# custom_pcb_schematic.net
KiCad netlist of a schematic drawn in Altium Designer
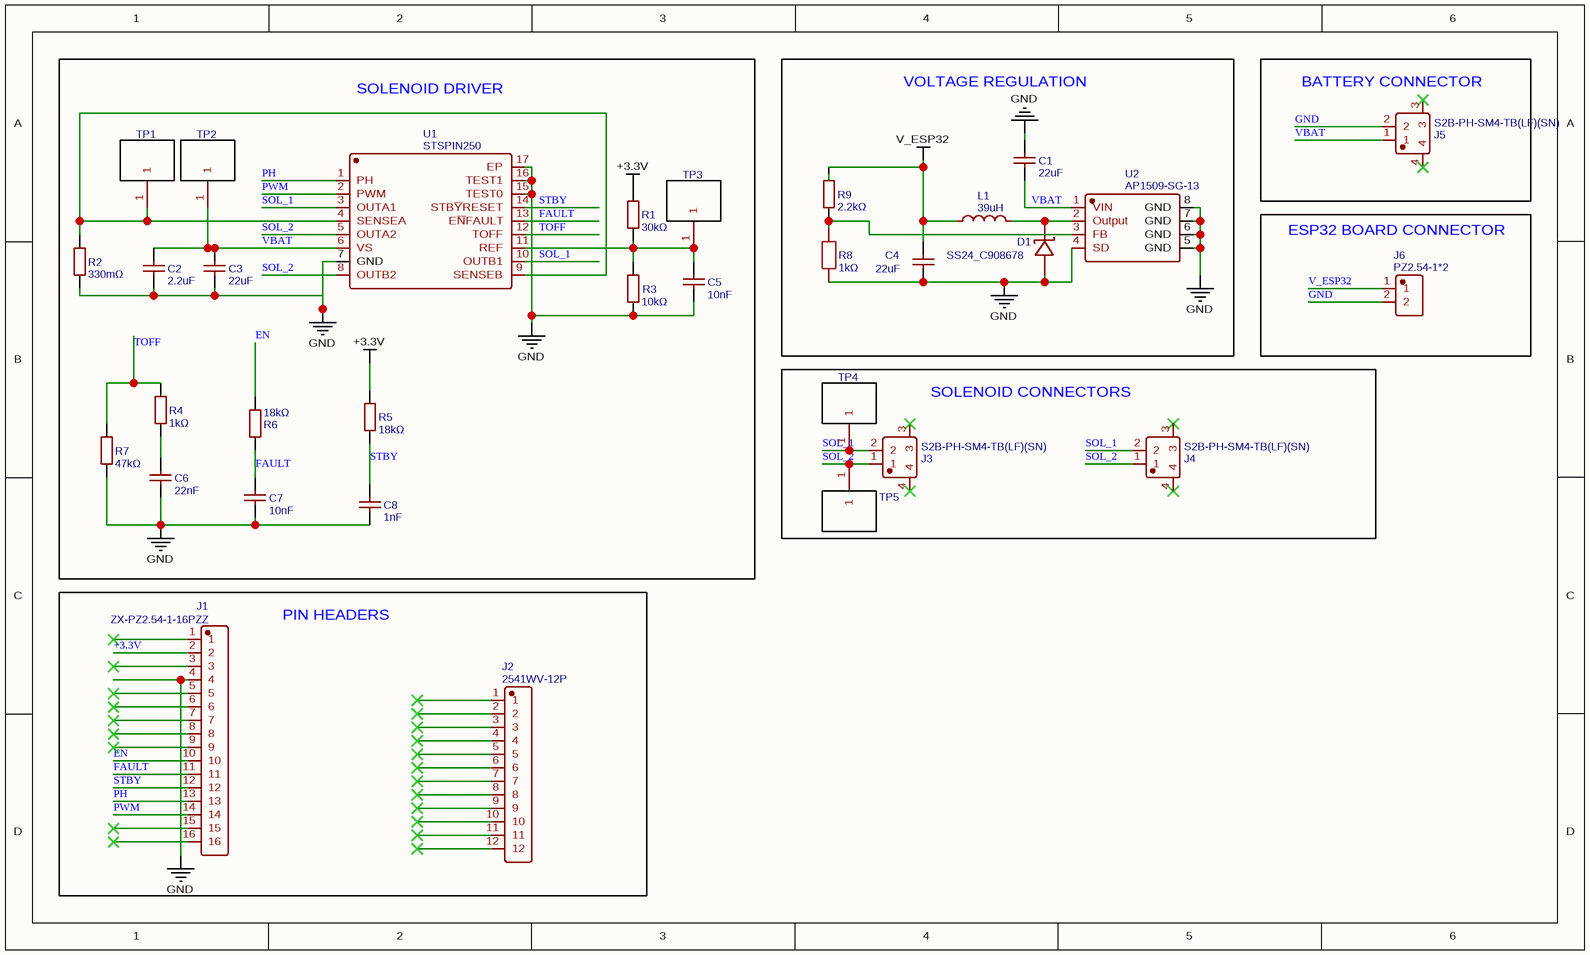
[diagram p0: custom_pcb_schematic.schdoc]

(export (version "E")
  (design (tool "Eeschema 10.0.6"))
  (components
    (comp (ref "C1")
      (value "22uF")
      (fields
        (field (name "MANUFACTURER") "SAMSUNG(三星)")
        (field (name "MANUFACTURER PART") "CL21A226MOQNNNE")
      )
      (libsource (lib "altium-import") (part "root_1_22uF_"))
    )
    (comp (ref "C2")
      (value "2.2uF")
      (fields
        (field (name "MANUFACTURER PART") "CL10A225KO8NNNC")
        (field (name "MANUFACTURER") "SAMSUNG(三星)")
      )
      (libsource (lib "altium-import") (part "root_1_2.2uF_"))
    )
    (comp (ref "C3")
      (value "22uF")
      (fields
        (field (name "MANUFACTURER") "SAMSUNG(三星)")
        (field (name "MANUFACTURER PART") "CL21A226MOQNNNE")
      )
      (libsource (lib "altium-import") (part "root_1_22uF_"))
    )
    (comp (ref "C4")
      (value "22uF")
      (fields
        (field (name "MANUFACTURER") "SAMSUNG(三星)")
        (field (name "MANUFACTURER PART") "CL21A226MOQNNNE")
      )
      (libsource (lib "altium-import") (part "root_1_22uF_"))
    )
    (comp (ref "C5")
      (value "10nF")
      (fields
        (field (name "MANUFACTURER PART") "CL10B103KB8NNNC")
        (field (name "MANUFACTURER") "SAMSUNG(三星)")
      )
      (libsource (lib "altium-import") (part "root_1_10nF_"))
    )
    (comp (ref "C6")
      (value "22nF")
      (fields
        (field (name "MANUFACTURER PART") "CL10B223KB8NNNC")
        (field (name "MANUFACTURER") "SAMSUNG(三星)")
      )
      (libsource (lib "altium-import") (part "root_1_22nF_"))
    )
    (comp (ref "C7")
      (value "10nF")
      (fields
        (field (name "MANUFACTURER PART") "CL10B103KB8NNNC")
        (field (name "MANUFACTURER") "SAMSUNG(三星)")
      )
      (libsource (lib "altium-import") (part "root_1_10nF_"))
    )
    (comp (ref "C8")
      (value "1nF")
      (fields
        (field (name "MANUFACTURER") "YAGEO(国巨)")
        (field (name "MANUFACTURER PART") "CC0402KRX7R9BB102")
        (field (name "CONTRIBUTOR") "LCSC")
      )
      (libsource (lib "altium-import") (part "root_1_1nF_"))
    )
    (comp (ref "D1")
      (value "SS24_C908678")
      (fields
        (field (name "MANUFACTURER") "GOODWORK(固得沃克)")
        (field (name "MANUFACTURER PART") "SS24")
        (field (name "CONTRIBUTOR") "lcsc")
      )
      (libsource (lib "altium-import") (part "root_3_SS24_C908678_"))
    )
    (comp (ref "J1")
      (value "ZX-PZ2.54-1-16PZZ")
      (fields (field (name "MANUFACTURER") "Megastar(兆星)") (field (name "CONTRIBUTOR") "lcsc"))
      (libsource (lib "altium-import") (part "root_0_ZX-PZ2.54-1-16PZZ_"))
    )
    (comp (ref "J2")
      (value "2541WV-12P")
      (fields (field (name "MANUFACTURER") "HanElectricity(瀚源)") (field (name "CONTRIBUTOR") "lcsc"))
      (libsource (lib "altium-import") (part "root_0_2541WV-12P_"))
    )
    (comp (ref "J3")
      (value "S2B-PH-SM4-TB(LF)(SN)")
      (fields (field (name "MANUFACTURER") "JST") (field (name "CONTRIBUTOR") "LCSC"))
      (libsource (lib "altium-import") (part "root_0_S2B-PH-SM4-TB(LF)(SN)_"))
    )
    (comp (ref "J4")
      (value "S2B-PH-SM4-TB(LF)(SN)")
      (fields (field (name "MANUFACTURER") "JST") (field (name "CONTRIBUTOR") "LCSC"))
      (libsource (lib "altium-import") (part "root_0_S2B-PH-SM4-TB(LF)(SN)_"))
    )
    (comp (ref "J5")
      (value "S2B-PH-SM4-TB(LF)(SN)")
      (fields (field (name "MANUFACTURER") "JST") (field (name "CONTRIBUTOR") "LCSC"))
      (libsource (lib "altium-import") (part "root_0_S2B-PH-SM4-TB(LF)(SN)_"))
    )
    (comp (ref "J6")
      (value "PZ2.54-1*2")
      (fields (field (name "MANUFACTURER") "ZHOURI(洲日)") (field (name "CONTRIBUTOR") "lcsc"))
      (libsource (lib "altium-import") (part "root_0_PZ2.54-1*2_"))
    )
    (comp (ref "L1")
      (value "39uH")
      (fields
        (field (name "MANUFACTURER") "YJYCOIN(益嘉源)")
        (field (name "MANUFACTURER PART") "YDRH104R-390M")
        (field (name "CONTRIBUTOR") "LCSC")
      )
      (libsource (lib "altium-import") (part "root_0_39uH_"))
    )
    (comp (ref "R1")
      (value "30kΩ")
      (fields (field (name "MANUFACTURER") "YAGEO(国巨)") (field (name "MANUFACTURER PART") "RC0402FR-0730KL"))
      (libsource (lib "altium-import") (part "root_1_30kΩ_"))
    )
    (comp (ref "R2")
      (value "330mΩ")
      (fields
        (field (name "MANUFACTURER") "UNI-ROYAL(厚声)")
        (field (name "MANUFACTURER PART") "25121WF330LT4E")
      )
      (libsource (lib "altium-import") (part "root_1_330mΩ_"))
    )
    (comp (ref "R3")
      (value "10kΩ")
      (fields
        (field (name "MANUFACTURER") "UNI-ROYAL(厚声)")
        (field (name "MANUFACTURER PART") "0603WAF1002T5E")
      )
      (libsource (lib "altium-import") (part "root_1_10kΩ_"))
    )
    (comp (ref "R4")
      (value "1kΩ")
      (fields (field (name "MANUFACTURER PART") "RC0603FR-071KL") (field (name "MANUFACTURER") "YAGEO(国巨)"))
      (libsource (lib "") (part "root_1_1kΩ__1"))
    )
    (comp (ref "R5")
      (value "18kΩ")
      (fields (field (name "MANUFACTURER") "YAGEO(国巨)") (field (name "MANUFACTURER PART") "RC0402FR-0718KL"))
      (libsource (lib "") (part "root_1_18kΩ__1"))
    )
    (comp (ref "R6")
      (value "18kΩ")
      (fields (field (name "MANUFACTURER") "YAGEO(国巨)") (field (name "MANUFACTURER PART") "RC0402FR-0718KL"))
      (libsource (lib "altium-import") (part "root_1_18kΩ_"))
    )
    (comp (ref "R7")
      (value "47kΩ")
      (fields (field (name "MANUFACTURER") "YAGEO(国巨)") (field (name "MANUFACTURER PART") "RC0402FR-0747KL"))
      (libsource (lib "altium-import") (part "root_1_47kΩ_"))
    )
    (comp (ref "R8")
      (value "1kΩ")
      (fields
        (field (name "MANUFACTURER") "VO(翔胜)")
        (field (name "MANUFACTURER PART") "SCR0603F1K")
        (field (name "CONTRIBUTOR") "lcsc")
      )
      (libsource (lib "altium-import") (part "root_1_1kΩ_"))
    )
    (comp (ref "R9")
      (value "2.2kΩ")
      (fields (field (name "MANUFACTURER") "YAGEO(国巨)") (field (name "MANUFACTURER PART") "RC0402FR-072K2L"))
      (libsource (lib "altium-import") (part "root_1_2.2kΩ_"))
    )
    (comp (ref "TP1")
      (value "PG2.0-4.5-0.8T")
      (fields (field (name "CONTRIBUTOR") "LCSC"))
      (libsource (lib "altium-import") (part "root_3_PG2.0-4.5-0.8T_"))
    )
    (comp (ref "TP2")
      (value "PG2.0-4.5-0.8T")
      (fields (field (name "CONTRIBUTOR") "LCSC"))
      (libsource (lib "altium-import") (part "root_3_PG2.0-4.5-0.8T_"))
    )
    (comp (ref "TP3")
      (value "PG2.0-4.5-0.8T")
      (fields (field (name "CONTRIBUTOR") "LCSC"))
      (libsource (lib "altium-import") (part "root_3_PG2.0-4.5-0.8T_"))
    )
    (comp (ref "TP4")
      (value "PG2.0-4.5-0.8T")
      (fields (field (name "CONTRIBUTOR") "LCSC"))
      (libsource (lib "altium-import") (part "root_3_PG2.0-4.5-0.8T_"))
    )
    (comp (ref "TP5")
      (value "PG2.0-4.5-0.8T")
      (fields (field (name "CONTRIBUTOR") "LCSC"))
      (libsource (lib "altium-import") (part "root_1_PG2.0-4.5-0.8T_"))
    )
    (comp (ref "U1")
      (value "STSPIN250")
      (fields (field (name "MANUFACTURER") "ST(意法半导体)") (field (name "CONTRIBUTOR") "LCSC"))
      (libsource (lib "altium-import") (part "root_0_STSPIN250_"))
    )
    (comp (ref "U2")
      (value "AP1509-SG-13")
      (fields (field (name "MANUFACTURER") "DIODES(美台)") (field (name "CONTRIBUTOR") "lcsc"))
      (libsource (lib "altium-import") (part "root_0_AP1509-SG-13_"))
    )
  )
  (nets
    (net (code "1") (name "+3.3V") (class "Default")
      (node (ref "J1") (pin "2") (pinfunction "2_2") (pintype "passive"))
      (node (ref "R1") (pin "2") (pinfunction "2_2") (pintype "passive"))
      (node (ref "R5") (pin "2") (pinfunction "2_2") (pintype "passive"))
    )
    (net (code "2") (name "/EN") (class "Default")
      (node (ref "J1") (pin "10") (pinfunction "10_10") (pintype "passive"))
      (node (ref "R6") (pin "1") (pinfunction "1_1") (pintype "passive"))
    )
    (net (code "3") (name "/FAULT") (class "Default")
      (node (ref "C7") (pin "2") (pinfunction "2_2") (pintype "passive"))
      (node (ref "J1") (pin "11") (pinfunction "11_11") (pintype "passive"))
      (node (ref "R6") (pin "2") (pinfunction "2_2") (pintype "passive"))
      (node (ref "U1") (pin "13") (pinfunction "E~{N}FAULT_13") (pintype "passive"))
    )
    (net (code "4") (name "/PH") (class "Default")
      (node (ref "J1") (pin "13") (pinfunction "13_13") (pintype "passive"))
      (node (ref "U1") (pin "1") (pinfunction "PH_1") (pintype "passive"))
    )
    (net (code "5") (name "/PWM") (class "Default")
      (node (ref "J1") (pin "14") (pinfunction "14_14") (pintype "passive"))
      (node (ref "U1") (pin "2") (pinfunction "PWM_2") (pintype "passive"))
    )
    (net (code "6") (name "/SOL_1") (class "Default")
      (node (ref "J3") (pin "2") (pinfunction "2_2") (pintype "passive"))
      (node (ref "J4") (pin "2") (pinfunction "2_2") (pintype "passive"))
      (node (ref "TP4") (pin "1") (pinfunction "1_1") (pintype "passive"))
      (node (ref "U1") (pin "10") (pinfunction "OUTB1_10") (pintype "passive"))
      (node (ref "U1") (pin "3") (pinfunction "OUTA1_3") (pintype "passive"))
    )
    (net (code "7") (name "/SOL_2") (class "Default")
      (node (ref "J3") (pin "1") (pinfunction "1_1") (pintype "passive"))
      (node (ref "J4") (pin "1") (pinfunction "1_1") (pintype "passive"))
      (node (ref "TP5") (pin "1") (pinfunction "1_1") (pintype "passive"))
      (node (ref "U1") (pin "5") (pinfunction "OUTA2_5") (pintype "passive"))
      (node (ref "U1") (pin "8") (pinfunction "OUTB2_8") (pintype "passive"))
    )
    (net (code "8") (name "/STBY") (class "Default")
      (node (ref "C8") (pin "2") (pinfunction "2_2") (pintype "passive"))
      (node (ref "J1") (pin "12") (pinfunction "12_12") (pintype "passive"))
      (node (ref "R5") (pin "1") (pinfunction "1_1") (pintype "passive"))
      (node (ref "U1") (pin "14") (pinfunction "STB~{Y}RESET_14") (pintype "passive"))
    )
    (net (code "9") (name "/TOFF") (class "Default")
      (node (ref "R4") (pin "2") (pinfunction "2_2") (pintype "passive"))
      (node (ref "R7") (pin "2") (pinfunction "2_2") (pintype "passive"))
      (node (ref "U1") (pin "12") (pinfunction "TOFF_12") (pintype "passive"))
    )
    (net (code "10") (name "/VBAT") (class "Default")
      (node (ref "C1") (pin "1") (pinfunction "1_1") (pintype "passive"))
      (node (ref "C2") (pin "2") (pinfunction "2_2") (pintype "passive"))
      (node (ref "C3") (pin "2") (pinfunction "2_2") (pintype "passive"))
      (node (ref "J5") (pin "1") (pinfunction "1_1") (pintype "passive"))
      (node (ref "TP2") (pin "1") (pinfunction "1_1") (pintype "passive"))
      (node (ref "U1") (pin "6") (pinfunction "VS_6") (pintype "passive"))
      (node (ref "U2") (pin "1") (pinfunction "VIN_1") (pintype "passive"))
    )
    (net (code "11") (name "GND") (class "Default")
      (node (ref "C1") (pin "2") (pinfunction "2_2") (pintype "passive"))
      (node (ref "C2") (pin "1") (pinfunction "1_1") (pintype "passive"))
      (node (ref "C3") (pin "1") (pinfunction "1_1") (pintype "passive"))
      (node (ref "C4") (pin "1") (pinfunction "1_1") (pintype "passive"))
      (node (ref "C5") (pin "1") (pinfunction "1_1") (pintype "passive"))
      (node (ref "C6") (pin "1") (pinfunction "1_1") (pintype "passive"))
      (node (ref "C7") (pin "1") (pinfunction "1_1") (pintype "passive"))
      (node (ref "C8") (pin "1") (pinfunction "1_1") (pintype "passive"))
      (node (ref "D1") (pin "2") (pinfunction "A_2") (pintype "passive"))
      (node (ref "J1") (pin "4") (pinfunction "4_4") (pintype "passive"))
      (node (ref "J5") (pin "2") (pinfunction "2_2") (pintype "passive"))
      (node (ref "J6") (pin "2") (pinfunction "2_2") (pintype "passive"))
      (node (ref "R2") (pin "1") (pinfunction "1_1") (pintype "passive"))
      (node (ref "R3") (pin "1") (pinfunction "1_1") (pintype "passive"))
      (node (ref "R7") (pin "1") (pinfunction "1_1") (pintype "passive"))
      (node (ref "R8") (pin "1") (pinfunction "1_1") (pintype "passive"))
      (node (ref "U1") (pin "15") (pinfunction "TEST0_15") (pintype "passive"))
      (node (ref "U1") (pin "16") (pinfunction "TEST1_16") (pintype "passive"))
      (node (ref "U1") (pin "17") (pinfunction "EP_17") (pintype "passive"))
      (node (ref "U1") (pin "7") (pinfunction "GND_7") (pintype "passive"))
      (node (ref "U2") (pin "4") (pinfunction "SD_4") (pintype "passive"))
      (node (ref "U2") (pin "5") (pinfunction "GND_5") (pintype "passive"))
      (node (ref "U2") (pin "6") (pinfunction "GND_6") (pintype "passive"))
      (node (ref "U2") (pin "7") (pinfunction "GND_7") (pintype "passive"))
      (node (ref "U2") (pin "8") (pinfunction "GND_8") (pintype "passive"))
    )
    (net (code "12") (name "Net-(C6-Pad2)") (class "Default")
      (node (ref "C6") (pin "2") (pinfunction "2_2") (pintype "passive"))
      (node (ref "R4") (pin "1") (pinfunction "1_1") (pintype "passive"))
    )
    (net (code "13") (name "Net-(D1-K)") (class "Default")
      (node (ref "D1") (pin "1") (pinfunction "K_1") (pintype "passive"))
      (node (ref "L1") (pin "2") (pinfunction "2_2") (pintype "passive"))
      (node (ref "U2") (pin "2") (pinfunction "Output_2") (pintype "passive"))
    )
    (net (code "14") (name "Net-(U1-REF)") (class "Default")
      (node (ref "C5") (pin "2") (pinfunction "2_2") (pintype "passive"))
      (node (ref "R1") (pin "1") (pinfunction "1_1") (pintype "passive"))
      (node (ref "R3") (pin "2") (pinfunction "2_2") (pintype "passive"))
      (node (ref "TP3") (pin "1") (pinfunction "1_1") (pintype "passive"))
      (node (ref "U1") (pin "11") (pinfunction "REF_11") (pintype "passive"))
    )
    (net (code "15") (name "Net-(U1-SENSEA)") (class "Default")
      (node (ref "R2") (pin "2") (pinfunction "2_2") (pintype "passive"))
      (node (ref "TP1") (pin "1") (pinfunction "1_1") (pintype "passive"))
      (node (ref "U1") (pin "4") (pinfunction "SENSEA_4") (pintype "passive"))
      (node (ref "U1") (pin "9") (pinfunction "SENSEB_9") (pintype "passive"))
    )
    (net (code "16") (name "Net-(U2-FB)") (class "Default")
      (node (ref "R8") (pin "2") (pinfunction "2_2") (pintype "passive"))
      (node (ref "R9") (pin "1") (pinfunction "1_1") (pintype "passive"))
      (node (ref "U2") (pin "3") (pinfunction "FB_3") (pintype "passive"))
    )
    (net (code "17") (name "V_ESP32") (class "Default")
      (node (ref "C4") (pin "2") (pinfunction "2_2") (pintype "passive"))
      (node (ref "J6") (pin "1") (pinfunction "1_1") (pintype "passive"))
      (node (ref "L1") (pin "1") (pinfunction "1_1") (pintype "passive"))
      (node (ref "R9") (pin "2") (pinfunction "2_2") (pintype "passive"))
    )
    (net (code "18") (name "unconnected-(J1-Pad1)") (class "Default")
      (node (ref "J1") (pin "1") (pinfunction "1_1") (pintype "passive+no_connect"))
    )
    (net (code "19") (name "unconnected-(J1-Pad3)") (class "Default")
      (node (ref "J1") (pin "3") (pinfunction "3_3") (pintype "passive+no_connect"))
    )
    (net (code "20") (name "unconnected-(J1-Pad5)") (class "Default")
      (node (ref "J1") (pin "5") (pinfunction "5_5") (pintype "passive+no_connect"))
    )
    (net (code "21") (name "unconnected-(J1-Pad6)") (class "Default")
      (node (ref "J1") (pin "6") (pinfunction "6_6") (pintype "passive+no_connect"))
    )
    (net (code "22") (name "unconnected-(J1-Pad7)") (class "Default")
      (node (ref "J1") (pin "7") (pinfunction "7_7") (pintype "passive+no_connect"))
    )
    (net (code "23") (name "unconnected-(J1-Pad8)") (class "Default")
      (node (ref "J1") (pin "8") (pinfunction "8_8") (pintype "passive+no_connect"))
    )
    (net (code "24") (name "unconnected-(J1-Pad9)") (class "Default")
      (node (ref "J1") (pin "9") (pinfunction "9_9") (pintype "passive+no_connect"))
    )
    (net (code "25") (name "unconnected-(J1-Pad15)") (class "Default")
      (node (ref "J1") (pin "15") (pinfunction "15_15") (pintype "passive+no_connect"))
    )
    (net (code "26") (name "unconnected-(J1-Pad16)") (class "Default")
      (node (ref "J1") (pin "16") (pinfunction "16_16") (pintype "passive+no_connect"))
    )
    (net (code "27") (name "unconnected-(J2-Pad1)") (class "Default")
      (node (ref "J2") (pin "1") (pinfunction "1_1") (pintype "passive+no_connect"))
    )
    (net (code "28") (name "unconnected-(J2-Pad2)") (class "Default")
      (node (ref "J2") (pin "2") (pinfunction "2_2") (pintype "passive+no_connect"))
    )
    (net (code "29") (name "unconnected-(J2-Pad3)") (class "Default")
      (node (ref "J2") (pin "3") (pinfunction "3_3") (pintype "passive+no_connect"))
    )
    (net (code "30") (name "unconnected-(J2-Pad4)") (class "Default")
      (node (ref "J2") (pin "4") (pinfunction "4_4") (pintype "passive+no_connect"))
    )
    (net (code "31") (name "unconnected-(J2-Pad5)") (class "Default")
      (node (ref "J2") (pin "5") (pinfunction "5_5") (pintype "passive+no_connect"))
    )
    (net (code "32") (name "unconnected-(J2-Pad6)") (class "Default")
      (node (ref "J2") (pin "6") (pinfunction "6_6") (pintype "passive+no_connect"))
    )
    (net (code "33") (name "unconnected-(J2-Pad7)") (class "Default")
      (node (ref "J2") (pin "7") (pinfunction "7_7") (pintype "passive+no_connect"))
    )
    (net (code "34") (name "unconnected-(J2-Pad8)") (class "Default")
      (node (ref "J2") (pin "8") (pinfunction "8_8") (pintype "passive+no_connect"))
    )
    (net (code "35") (name "unconnected-(J2-Pad9)") (class "Default")
      (node (ref "J2") (pin "9") (pinfunction "9_9") (pintype "passive+no_connect"))
    )
    (net (code "36") (name "unconnected-(J2-Pad10)") (class "Default")
      (node (ref "J2") (pin "10") (pinfunction "10_10") (pintype "passive+no_connect"))
    )
    (net (code "37") (name "unconnected-(J2-Pad11)") (class "Default")
      (node (ref "J2") (pin "11") (pinfunction "11_11") (pintype "passive+no_connect"))
    )
    (net (code "38") (name "unconnected-(J2-Pad12)") (class "Default")
      (node (ref "J2") (pin "12") (pinfunction "12_12") (pintype "passive+no_connect"))
    )
    (net (code "39") (name "unconnected-(J3-Pad3)") (class "Default")
      (node (ref "J3") (pin "3") (pinfunction "3_3") (pintype "passive+no_connect"))
    )
    (net (code "40") (name "unconnected-(J3-Pad4)") (class "Default")
      (node (ref "J3") (pin "4") (pinfunction "4_4") (pintype "passive+no_connect"))
    )
    (net (code "41") (name "unconnected-(J4-Pad3)") (class "Default")
      (node (ref "J4") (pin "3") (pinfunction "3_3") (pintype "passive+no_connect"))
    )
    (net (code "42") (name "unconnected-(J4-Pad4)") (class "Default")
      (node (ref "J4") (pin "4") (pinfunction "4_4") (pintype "passive+no_connect"))
    )
    (net (code "43") (name "unconnected-(J5-Pad3)") (class "Default")
      (node (ref "J5") (pin "3") (pinfunction "3_3") (pintype "passive+no_connect"))
    )
    (net (code "44") (name "unconnected-(J5-Pad4)") (class "Default")
      (node (ref "J5") (pin "4") (pinfunction "4_4") (pintype "passive+no_connect"))
    )
  )
)
